# cdf-dual-driver.net
KiCad netlist of a schematic drawn in EAGLE
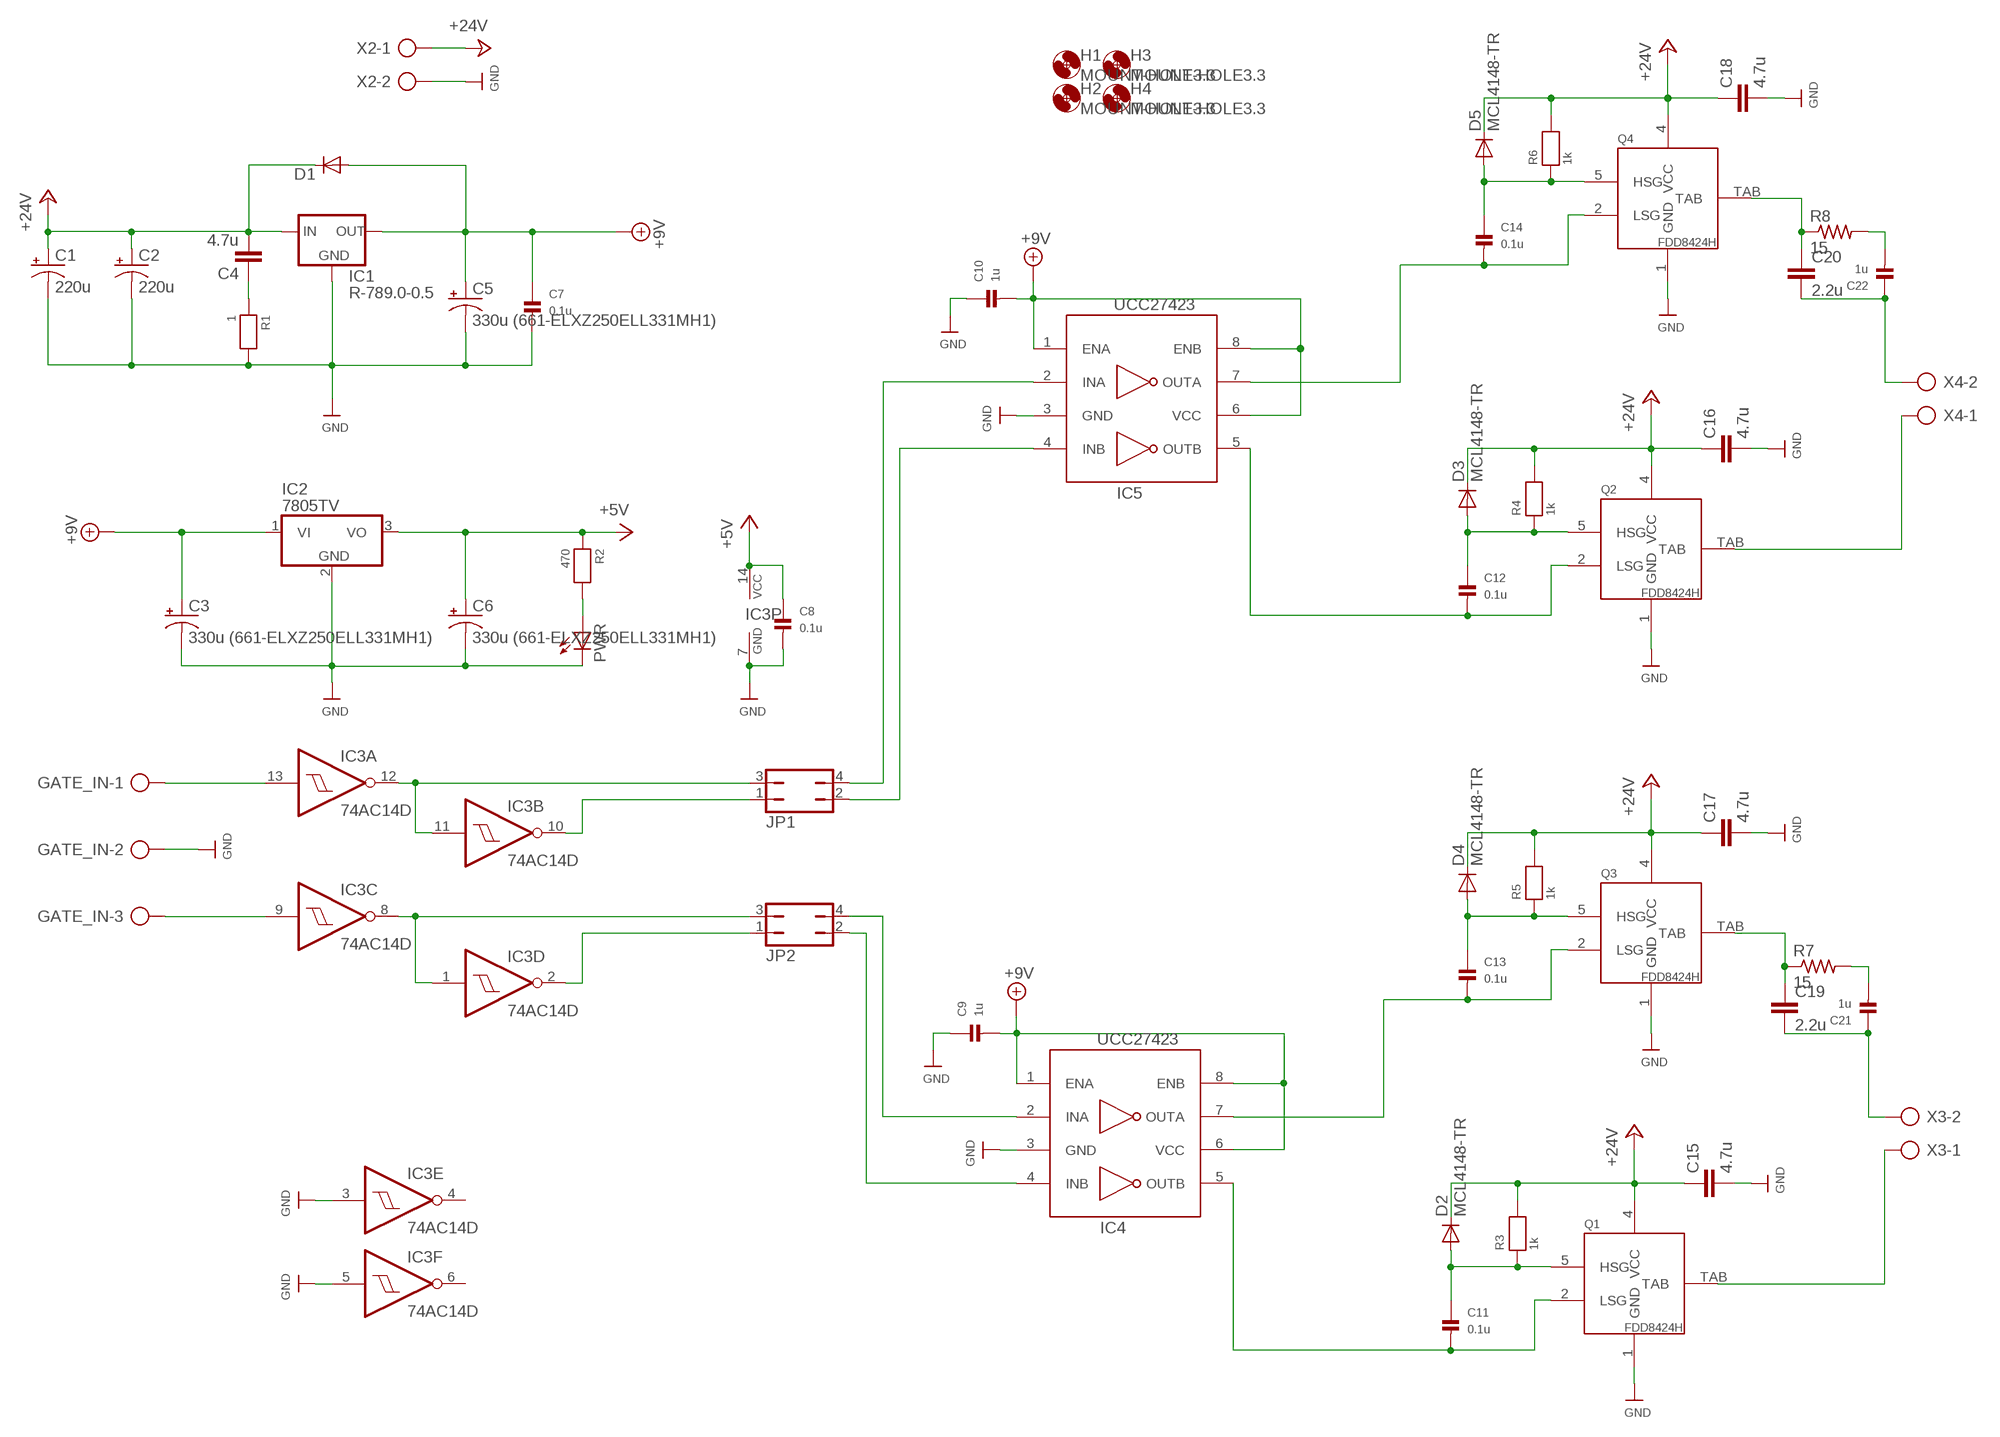
[diagram p0: schematic, sheet 1]

(export (version "E")
  (design (tool "Eeschema 10.0.6"))
  (components
    (comp (ref "C1")
      (value "220u")
      (footprint "eagle-import:E3,5-8")
      (libsource (lib "eagle-import") (part "CPOL-USE3.5-8"))
    )
    (comp (ref "C2")
      (value "220u")
      (footprint "eagle-import:E3,5-8")
      (libsource (lib "eagle-import") (part "CPOL-USE3.5-8"))
    )
    (comp (ref "C3")
      (value "330u (661-ELXZ250ELL331MH1)")
      (footprint "eagle-import:E3,5-8")
      (libsource (lib "eagle-import") (part "CPOL-USE3.5-8"))
    )
    (comp (ref "C4")
      (value "4.7u")
      (footprint "eagle-import:C1210")
      (libsource (lib "eagle-import") (part "C-EUC1210"))
    )
    (comp (ref "C5")
      (value "330u (661-ELXZ250ELL331MH1)")
      (footprint "eagle-import:E3,5-8")
      (libsource (lib "eagle-import") (part "CPOL-USE3.5-8"))
    )
    (comp (ref "C6")
      (value "330u (661-ELXZ250ELL331MH1)")
      (footprint "eagle-import:E3,5-8")
      (libsource (lib "eagle-import") (part "CPOL-USE3.5-8"))
    )
    (comp (ref "C7")
      (value "0.1u")
      (footprint "eagle-import:0805")
      (libsource (lib "eagle-import") (part "CAP_CERAMIC0805"))
    )
    (comp (ref "C8")
      (value "0.1u")
      (footprint "eagle-import:0805")
      (libsource (lib "eagle-import") (part "CAP_CERAMIC0805"))
    )
    (comp (ref "C9")
      (value "1u")
      (footprint "eagle-import:1206")
      (libsource (lib "eagle-import") (part "CAP_CERAMIC1206"))
    )
    (comp (ref "C10")
      (value "1u")
      (footprint "eagle-import:1206")
      (libsource (lib "eagle-import") (part "CAP_CERAMIC1206"))
    )
    (comp (ref "C11")
      (value "0.1u")
      (footprint "eagle-import:0805")
      (libsource (lib "eagle-import") (part "CAP_CERAMIC0805"))
    )
    (comp (ref "C12")
      (value "0.1u")
      (footprint "eagle-import:0805")
      (libsource (lib "eagle-import") (part "CAP_CERAMIC0805"))
    )
    (comp (ref "C13")
      (value "0.1u")
      (footprint "eagle-import:0805")
      (libsource (lib "eagle-import") (part "CAP_CERAMIC0805"))
    )
    (comp (ref "C14")
      (value "0.1u")
      (footprint "eagle-import:0805")
      (libsource (lib "eagle-import") (part "CAP_CERAMIC0805"))
    )
    (comp (ref "C15")
      (value "4.7u")
      (footprint "eagle-import:C1210")
      (libsource (lib "eagle-import") (part "C-EUC1210"))
    )
    (comp (ref "C16")
      (value "4.7u")
      (footprint "eagle-import:C1210")
      (libsource (lib "eagle-import") (part "C-EUC1210"))
    )
    (comp (ref "C17")
      (value "4.7u")
      (footprint "eagle-import:C1210")
      (libsource (lib "eagle-import") (part "C-EUC1210"))
    )
    (comp (ref "C18")
      (value "4.7u")
      (footprint "eagle-import:C1210")
      (libsource (lib "eagle-import") (part "C-EUC1210"))
    )
    (comp (ref "C19")
      (value "2.2u")
      (footprint "eagle-import:C1210")
      (libsource (lib "eagle-import") (part "C-EUC1210"))
    )
    (comp (ref "C20")
      (value "2.2u")
      (footprint "eagle-import:C1210")
      (libsource (lib "eagle-import") (part "C-EUC1210"))
    )
    (comp (ref "C21")
      (value "1u")
      (footprint "eagle-import:1206")
      (libsource (lib "eagle-import") (part "CAP_CERAMIC1206"))
    )
    (comp (ref "C22")
      (value "1u")
      (footprint "eagle-import:1206")
      (libsource (lib "eagle-import") (part "CAP_CERAMIC1206"))
    )
    (comp (ref "D1")
      (value "DIODE-SOD123")
      (footprint "eagle-import:SOD123")
      (libsource (lib "eagle-import") (part "DIODE-SOD123"))
    )
    (comp (ref "D2")
      (value "MCL4148-TR")
      (footprint "eagle-import:MICROMELF-W")
      (libsource (lib "eagle-import") (part "DIODE-MICROMELF-W"))
    )
    (comp (ref "D3")
      (value "MCL4148-TR")
      (footprint "eagle-import:MICROMELF-W")
      (libsource (lib "eagle-import") (part "DIODE-MICROMELF-W"))
    )
    (comp (ref "D4")
      (value "MCL4148-TR")
      (footprint "eagle-import:MICROMELF-W")
      (libsource (lib "eagle-import") (part "DIODE-MICROMELF-W"))
    )
    (comp (ref "D5")
      (value "MCL4148-TR")
      (footprint "eagle-import:MICROMELF-W")
      (libsource (lib "eagle-import") (part "DIODE-MICROMELF-W"))
    )
    (comp (ref "GATE_IN")
      (value "AK500/3")
      (footprint "eagle-import:AK500_3")
      (libsource (lib "eagle-import") (part "AK500/3"))
    )
    (comp (ref "H1")
      (value "MOUNT-HOLE3.3")
      (footprint "eagle-import:3,3")
      (libsource (lib "eagle-import") (part "MOUNT-HOLE3.3"))
    )
    (comp (ref "H2")
      (value "MOUNT-HOLE3.3")
      (footprint "eagle-import:3,3")
      (libsource (lib "eagle-import") (part "MOUNT-HOLE3.3"))
    )
    (comp (ref "H3")
      (value "MOUNT-HOLE3.3")
      (footprint "eagle-import:3,3")
      (libsource (lib "eagle-import") (part "MOUNT-HOLE3.3"))
    )
    (comp (ref "H4")
      (value "MOUNT-HOLE3.3")
      (footprint "eagle-import:3,3")
      (libsource (lib "eagle-import") (part "MOUNT-HOLE3.3"))
    )
    (comp (ref "IC1")
      (value "R-789.0-0.5")
      (footprint "eagle-import:SIP3")
      (fields (field (name "MF") "Recom") (field (name "MPN") "R-789.0-05"))
      (libsource (lib "eagle-import") (part "R-78-0.59.0"))
    )
    (comp (ref "IC2")
      (value "7805TV")
      (footprint "eagle-import:TO220V")
      (libsource (lib "eagle-import") (part "78TV05"))
    )
    (comp (ref "IC3")
      (value "74AC14D")
      (footprint "eagle-import:SO14")
      (libsource (lib "eagle-import") (part "7414DAC"))
    )
    (comp (ref "IC4")
      (value "UCC27423")
      (footprint "eagle-import:SOIC8")
      (libsource (lib "eagle-import") (part "UCC27423"))
    )
    (comp (ref "IC5")
      (value "UCC27423")
      (footprint "eagle-import:SOIC8")
      (libsource (lib "eagle-import") (part "UCC27423"))
    )
    (comp (ref "JP1")
      (value "JP2Q")
      (footprint "eagle-import:JP2Q")
      (libsource (lib "eagle-import") (part "JP2Q"))
    )
    (comp (ref "JP2")
      (value "JP2Q")
      (footprint "eagle-import:JP2Q")
      (libsource (lib "eagle-import") (part "JP2Q"))
    )
    (comp (ref "PWR")
      (value "LED5MM")
      (footprint "eagle-import:LED5MM")
      (libsource (lib "eagle-import") (part "LED5MM"))
    )
    (comp (ref "Q1")
      (value "FDD8424H")
      (footprint "eagle-import:TO252-4")
      (libsource (lib "eagle-import") (part "FDD8424H"))
    )
    (comp (ref "Q2")
      (value "FDD8424H")
      (footprint "eagle-import:TO252-4")
      (libsource (lib "eagle-import") (part "FDD8424H"))
    )
    (comp (ref "Q3")
      (value "FDD8424H")
      (footprint "eagle-import:TO252-4")
      (libsource (lib "eagle-import") (part "FDD8424H"))
    )
    (comp (ref "Q4")
      (value "FDD8424H")
      (footprint "eagle-import:TO252-4")
      (libsource (lib "eagle-import") (part "FDD8424H"))
    )
    (comp (ref "R1")
      (value "1")
      (footprint "eagle-import:0805")
      (libsource (lib "eagle-import") (part "RESISTOR0805"))
    )
    (comp (ref "R2")
      (value "470")
      (footprint "eagle-import:0805")
      (libsource (lib "eagle-import") (part "RESISTOR0805"))
    )
    (comp (ref "R3")
      (value "1k")
      (footprint "eagle-import:0805")
      (libsource (lib "eagle-import") (part "RESISTOR0805"))
    )
    (comp (ref "R4")
      (value "1k")
      (footprint "eagle-import:0805")
      (libsource (lib "eagle-import") (part "RESISTOR0805"))
    )
    (comp (ref "R5")
      (value "1k")
      (footprint "eagle-import:0805")
      (libsource (lib "eagle-import") (part "RESISTOR0805"))
    )
    (comp (ref "R6")
      (value "1k")
      (footprint "eagle-import:0805")
      (libsource (lib "eagle-import") (part "RESISTOR0805"))
    )
    (comp (ref "R7")
      (value "15")
      (footprint "eagle-import:R1210")
      (libsource (lib "eagle-import") (part "R-US_R1210"))
    )
    (comp (ref "R8")
      (value "15")
      (footprint "eagle-import:R1210")
      (libsource (lib "eagle-import") (part "R-US_R1210"))
    )
    (comp (ref "X2")
      (value "AK500/2")
      (footprint "eagle-import:AK500_2")
      (libsource (lib "eagle-import") (part "AK500/2"))
    )
    (comp (ref "X3")
      (value "AK500/2")
      (footprint "eagle-import:AK500_2")
      (libsource (lib "eagle-import") (part "AK500/2"))
    )
    (comp (ref "X4")
      (value "AK500/2")
      (footprint "eagle-import:AK500_2")
      (libsource (lib "eagle-import") (part "AK500/2"))
    )
  )
  (nets
    (net (code "1") (name "+5V") (class "Default")
      (node (ref "C6") (pin "+") (pinfunction "+_+") (pintype "passive"))
      (node (ref "C8") (pin "1") (pinfunction "P$1_1") (pintype "passive"))
      (node (ref "IC2") (pin "3") (pinfunction "VO_3") (pintype "passive"))
      (node (ref "IC3") (pin "14") (pinfunction "VCC_14") (pintype "power_in"))
      (node (ref "R2") (pin "1") (pinfunction "1_1") (pintype "passive"))
    )
    (net (code "2") (name "+9V") (class "Default")
      (node (ref "C10") (pin "2") (pinfunction "P$2_2") (pintype "passive"))
      (node (ref "C3") (pin "+") (pinfunction "+_+") (pintype "passive"))
      (node (ref "C5") (pin "+") (pinfunction "+_+") (pintype "passive"))
      (node (ref "C7") (pin "1") (pinfunction "P$1_1") (pintype "passive"))
      (node (ref "C9") (pin "2") (pinfunction "P$2_2") (pintype "passive"))
      (node (ref "D1") (pin "A") (pinfunction "A_A") (pintype "passive"))
      (node (ref "IC1") (pin "3") (pinfunction "OUT_3") (pintype "passive"))
      (node (ref "IC2") (pin "1") (pinfunction "VI_1") (pintype "input"))
      (node (ref "IC4") (pin "1") (pinfunction "ENA_1") (pintype "bidirectional"))
      (node (ref "IC4") (pin "6") (pinfunction "VCC_6") (pintype "bidirectional"))
      (node (ref "IC4") (pin "8") (pinfunction "ENB_8") (pintype "bidirectional"))
      (node (ref "IC5") (pin "1") (pinfunction "ENA_1") (pintype "bidirectional"))
      (node (ref "IC5") (pin "6") (pinfunction "VCC_6") (pintype "bidirectional"))
      (node (ref "IC5") (pin "8") (pinfunction "ENB_8") (pintype "bidirectional"))
    )
    (net (code "3") (name "+24V") (class "Default")
      (node (ref "C1") (pin "+") (pinfunction "+_+") (pintype "passive"))
      (node (ref "C15") (pin "1") (pinfunction "1_1") (pintype "passive"))
      (node (ref "C16") (pin "1") (pinfunction "1_1") (pintype "passive"))
      (node (ref "C17") (pin "1") (pinfunction "1_1") (pintype "passive"))
      (node (ref "C18") (pin "1") (pinfunction "1_1") (pintype "passive"))
      (node (ref "C2") (pin "+") (pinfunction "+_+") (pintype "passive"))
      (node (ref "C4") (pin "2") (pinfunction "2_2") (pintype "passive"))
      (node (ref "D1") (pin "C") (pinfunction "C_C") (pintype "passive"))
      (node (ref "D2") (pin "C") (pinfunction "C_C") (pintype "passive"))
      (node (ref "D3") (pin "C") (pinfunction "C_C") (pintype "passive"))
      (node (ref "D4") (pin "C") (pinfunction "C_C") (pintype "passive"))
      (node (ref "D5") (pin "C") (pinfunction "C_C") (pintype "passive"))
      (node (ref "IC1") (pin "1") (pinfunction "IN_1") (pintype "input"))
      (node (ref "Q1") (pin "4") (pinfunction "VCC_4") (pintype "bidirectional"))
      (node (ref "Q2") (pin "4") (pinfunction "VCC_4") (pintype "bidirectional"))
      (node (ref "Q3") (pin "4") (pinfunction "VCC_4") (pintype "bidirectional"))
      (node (ref "Q4") (pin "4") (pinfunction "VCC_4") (pintype "bidirectional"))
      (node (ref "R3") (pin "2") (pinfunction "2_2") (pintype "passive"))
      (node (ref "R4") (pin "2") (pinfunction "2_2") (pintype "passive"))
      (node (ref "R5") (pin "2") (pinfunction "2_2") (pintype "passive"))
      (node (ref "R6") (pin "2") (pinfunction "2_2") (pintype "passive"))
      (node (ref "X2") (pin "1") (pinfunction "KL_1") (pintype "passive"))
    )
    (net (code "4") (name "GND") (class "Default")
      (node (ref "C1") (pin "-") (pinfunction "-_-") (pintype "passive"))
      (node (ref "C10") (pin "1") (pinfunction "P$1_1") (pintype "passive"))
      (node (ref "C15") (pin "2") (pinfunction "2_2") (pintype "passive"))
      (node (ref "C16") (pin "2") (pinfunction "2_2") (pintype "passive"))
      (node (ref "C17") (pin "2") (pinfunction "2_2") (pintype "passive"))
      (node (ref "C18") (pin "2") (pinfunction "2_2") (pintype "passive"))
      (node (ref "C2") (pin "-") (pinfunction "-_-") (pintype "passive"))
      (node (ref "C3") (pin "-") (pinfunction "-_-") (pintype "passive"))
      (node (ref "C5") (pin "-") (pinfunction "-_-") (pintype "passive"))
      (node (ref "C6") (pin "-") (pinfunction "-_-") (pintype "passive"))
      (node (ref "C7") (pin "2") (pinfunction "P$2_2") (pintype "passive"))
      (node (ref "C8") (pin "2") (pinfunction "P$2_2") (pintype "passive"))
      (node (ref "C9") (pin "1") (pinfunction "P$1_1") (pintype "passive"))
      (node (ref "GATE_IN") (pin "2") (pinfunction "KL_2") (pintype "passive"))
      (node (ref "IC1") (pin "2") (pinfunction "GND_2") (pintype "input"))
      (node (ref "IC2") (pin "2") (pinfunction "GND_2") (pintype "passive"))
      (node (ref "IC3") (pin "3") (pinfunction "I_3") (pintype "input"))
      (node (ref "IC3") (pin "5") (pinfunction "I_5") (pintype "input"))
      (node (ref "IC3") (pin "7") (pinfunction "GND_7") (pintype "power_in"))
      (node (ref "IC4") (pin "3") (pinfunction "GND_3") (pintype "bidirectional"))
      (node (ref "IC5") (pin "3") (pinfunction "GND_3") (pintype "bidirectional"))
      (node (ref "PWR") (pin "K") (pinfunction "C_K") (pintype "passive"))
      (node (ref "Q1") (pin "1") (pinfunction "GND_1") (pintype "bidirectional"))
      (node (ref "Q2") (pin "1") (pinfunction "GND_1") (pintype "bidirectional"))
      (node (ref "Q3") (pin "1") (pinfunction "GND_1") (pintype "bidirectional"))
      (node (ref "Q4") (pin "1") (pinfunction "GND_1") (pintype "bidirectional"))
      (node (ref "R1") (pin "2") (pinfunction "2_2") (pintype "passive"))
      (node (ref "X2") (pin "2") (pinfunction "KL_2") (pintype "passive"))
    )
    (net (code "5") (name "Net-(C4-Pad1)") (class "Default")
      (node (ref "C4") (pin "1") (pinfunction "1_1") (pintype "passive"))
      (node (ref "R1") (pin "1") (pinfunction "1_1") (pintype "passive"))
    )
    (net (code "6") (name "Net-(C11-P$1)") (class "Default")
      (node (ref "C11") (pin "1") (pinfunction "P$1_1") (pintype "passive"))
      (node (ref "D2") (pin "A") (pinfunction "A_A") (pintype "passive"))
      (node (ref "Q1") (pin "5") (pinfunction "HSG_5") (pintype "bidirectional"))
      (node (ref "R3") (pin "1") (pinfunction "1_1") (pintype "passive"))
    )
    (net (code "7") (name "Net-(C11-P$2)") (class "Default")
      (node (ref "C11") (pin "2") (pinfunction "P$2_2") (pintype "passive"))
      (node (ref "IC4") (pin "5") (pinfunction "OUTB_5") (pintype "bidirectional"))
      (node (ref "Q1") (pin "2") (pinfunction "LSG_2") (pintype "bidirectional"))
    )
    (net (code "8") (name "Net-(C12-P$1)") (class "Default")
      (node (ref "C12") (pin "1") (pinfunction "P$1_1") (pintype "passive"))
      (node (ref "D3") (pin "A") (pinfunction "A_A") (pintype "passive"))
      (node (ref "Q2") (pin "5") (pinfunction "HSG_5") (pintype "bidirectional"))
      (node (ref "R4") (pin "1") (pinfunction "1_1") (pintype "passive"))
    )
    (net (code "9") (name "Net-(C12-P$2)") (class "Default")
      (node (ref "C12") (pin "2") (pinfunction "P$2_2") (pintype "passive"))
      (node (ref "IC5") (pin "5") (pinfunction "OUTB_5") (pintype "bidirectional"))
      (node (ref "Q2") (pin "2") (pinfunction "LSG_2") (pintype "bidirectional"))
    )
    (net (code "10") (name "Net-(C13-P$1)") (class "Default")
      (node (ref "C13") (pin "1") (pinfunction "P$1_1") (pintype "passive"))
      (node (ref "D4") (pin "A") (pinfunction "A_A") (pintype "passive"))
      (node (ref "Q3") (pin "5") (pinfunction "HSG_5") (pintype "bidirectional"))
      (node (ref "R5") (pin "1") (pinfunction "1_1") (pintype "passive"))
    )
    (net (code "11") (name "Net-(C13-P$2)") (class "Default")
      (node (ref "C13") (pin "2") (pinfunction "P$2_2") (pintype "passive"))
      (node (ref "IC4") (pin "7") (pinfunction "OUTA_7") (pintype "bidirectional"))
      (node (ref "Q3") (pin "2") (pinfunction "LSG_2") (pintype "bidirectional"))
    )
    (net (code "12") (name "Net-(C14-P$1)") (class "Default")
      (node (ref "C14") (pin "1") (pinfunction "P$1_1") (pintype "passive"))
      (node (ref "D5") (pin "A") (pinfunction "A_A") (pintype "passive"))
      (node (ref "Q4") (pin "5") (pinfunction "HSG_5") (pintype "bidirectional"))
      (node (ref "R6") (pin "1") (pinfunction "1_1") (pintype "passive"))
    )
    (net (code "13") (name "Net-(C14-P$2)") (class "Default")
      (node (ref "C14") (pin "2") (pinfunction "P$2_2") (pintype "passive"))
      (node (ref "IC5") (pin "7") (pinfunction "OUTA_7") (pintype "bidirectional"))
      (node (ref "Q4") (pin "2") (pinfunction "LSG_2") (pintype "bidirectional"))
    )
    (net (code "14") (name "Net-(C19-Pad1)") (class "Default")
      (node (ref "C19") (pin "1") (pinfunction "1_1") (pintype "passive"))
      (node (ref "Q3") (pin "TAB") (pinfunction "TAB_TAB") (pintype "bidirectional"))
      (node (ref "R7") (pin "1") (pinfunction "1_1") (pintype "passive"))
    )
    (net (code "15") (name "Net-(C20-Pad1)") (class "Default")
      (node (ref "C20") (pin "1") (pinfunction "1_1") (pintype "passive"))
      (node (ref "Q4") (pin "TAB") (pinfunction "TAB_TAB") (pintype "bidirectional"))
      (node (ref "R8") (pin "1") (pinfunction "1_1") (pintype "passive"))
    )
    (net (code "16") (name "Net-(C21-P$1)") (class "Default")
      (node (ref "C19") (pin "2") (pinfunction "2_2") (pintype "passive"))
      (node (ref "C21") (pin "1") (pinfunction "P$1_1") (pintype "passive"))
      (node (ref "X3") (pin "2") (pinfunction "KL_2") (pintype "passive"))
    )
    (net (code "17") (name "Net-(C21-P$2)") (class "Default")
      (node (ref "C21") (pin "2") (pinfunction "P$2_2") (pintype "passive"))
      (node (ref "R7") (pin "2") (pinfunction "2_2") (pintype "passive"))
    )
    (net (code "18") (name "Net-(C22-P$1)") (class "Default")
      (node (ref "C20") (pin "2") (pinfunction "2_2") (pintype "passive"))
      (node (ref "C22") (pin "1") (pinfunction "P$1_1") (pintype "passive"))
      (node (ref "X4") (pin "2") (pinfunction "KL_2") (pintype "passive"))
    )
    (net (code "19") (name "Net-(C22-P$2)") (class "Default")
      (node (ref "C22") (pin "2") (pinfunction "P$2_2") (pintype "passive"))
      (node (ref "R8") (pin "2") (pinfunction "2_2") (pintype "passive"))
    )
    (net (code "20") (name "Net-(GATE_INA-KL)") (class "Default")
      (node (ref "GATE_IN") (pin "1") (pinfunction "KL_1") (pintype "passive"))
      (node (ref "IC3") (pin "13") (pinfunction "I_13") (pintype "input"))
    )
    (net (code "21") (name "Net-(GATE_INC-KL)") (class "Default")
      (node (ref "GATE_IN") (pin "3") (pinfunction "KL_3") (pintype "passive"))
      (node (ref "IC3") (pin "9") (pinfunction "I_9") (pintype "input"))
    )
    (net (code "22") (name "Net-(IC3A-O)") (class "Default")
      (node (ref "IC3") (pin "11") (pinfunction "I_11") (pintype "input"))
      (node (ref "IC3") (pin "12") (pinfunction "O_12") (pintype "output"))
      (node (ref "JP1") (pin "3") (pinfunction "3_3") (pintype "passive"))
    )
    (net (code "23") (name "Net-(IC3B-O)") (class "Default")
      (node (ref "IC3") (pin "10") (pinfunction "O_10") (pintype "output"))
      (node (ref "JP1") (pin "1") (pinfunction "1_1") (pintype "passive"))
    )
    (net (code "24") (name "Net-(IC3C-O)") (class "Default")
      (node (ref "IC3") (pin "1") (pinfunction "I_1") (pintype "input"))
      (node (ref "IC3") (pin "8") (pinfunction "O_8") (pintype "output"))
      (node (ref "JP2") (pin "3") (pinfunction "3_3") (pintype "passive"))
    )
    (net (code "25") (name "Net-(IC3D-O)") (class "Default")
      (node (ref "IC3") (pin "2") (pinfunction "O_2") (pintype "output"))
      (node (ref "JP2") (pin "1") (pinfunction "1_1") (pintype "passive"))
    )
    (net (code "26") (name "Net-(IC4-INA)") (class "Default")
      (node (ref "IC4") (pin "2") (pinfunction "INA_2") (pintype "bidirectional"))
      (node (ref "JP2") (pin "4") (pinfunction "4_4") (pintype "passive"))
    )
    (net (code "27") (name "Net-(IC4-INB)") (class "Default")
      (node (ref "IC4") (pin "4") (pinfunction "INB_4") (pintype "bidirectional"))
      (node (ref "JP2") (pin "2") (pinfunction "2_2") (pintype "passive"))
    )
    (net (code "28") (name "Net-(IC5-INA)") (class "Default")
      (node (ref "IC5") (pin "2") (pinfunction "INA_2") (pintype "bidirectional"))
      (node (ref "JP1") (pin "4") (pinfunction "4_4") (pintype "passive"))
    )
    (net (code "29") (name "Net-(IC5-INB)") (class "Default")
      (node (ref "IC5") (pin "4") (pinfunction "INB_4") (pintype "bidirectional"))
      (node (ref "JP1") (pin "2") (pinfunction "2_2") (pintype "passive"))
    )
    (net (code "30") (name "Net-(PWR-PadA)") (class "Default")
      (node (ref "PWR") (pin "A") (pinfunction "A_A") (pintype "passive"))
      (node (ref "R2") (pin "2") (pinfunction "2_2") (pintype "passive"))
    )
    (net (code "31") (name "Net-(X3A-KL)") (class "Default")
      (node (ref "Q1") (pin "TAB") (pinfunction "TAB_TAB") (pintype "bidirectional"))
      (node (ref "X3") (pin "1") (pinfunction "KL_1") (pintype "passive"))
    )
    (net (code "32") (name "Net-(X4A-KL)") (class "Default")
      (node (ref "Q2") (pin "TAB") (pinfunction "TAB_TAB") (pintype "bidirectional"))
      (node (ref "X4") (pin "1") (pinfunction "KL_1") (pintype "passive"))
    )
    (net (code "33") (name "unconnected-(IC3E-O-Pad4)") (class "Default")
      (node (ref "IC3") (pin "4") (pinfunction "O_4") (pintype "output"))
    )
    (net (code "34") (name "unconnected-(IC3F-O-Pad6)") (class "Default")
      (node (ref "IC3") (pin "6") (pinfunction "O_6") (pintype "output"))
    )
  )
)
